# sensor_flexconn.net
KiCad netlist of a schematic drawn in Altium Designer
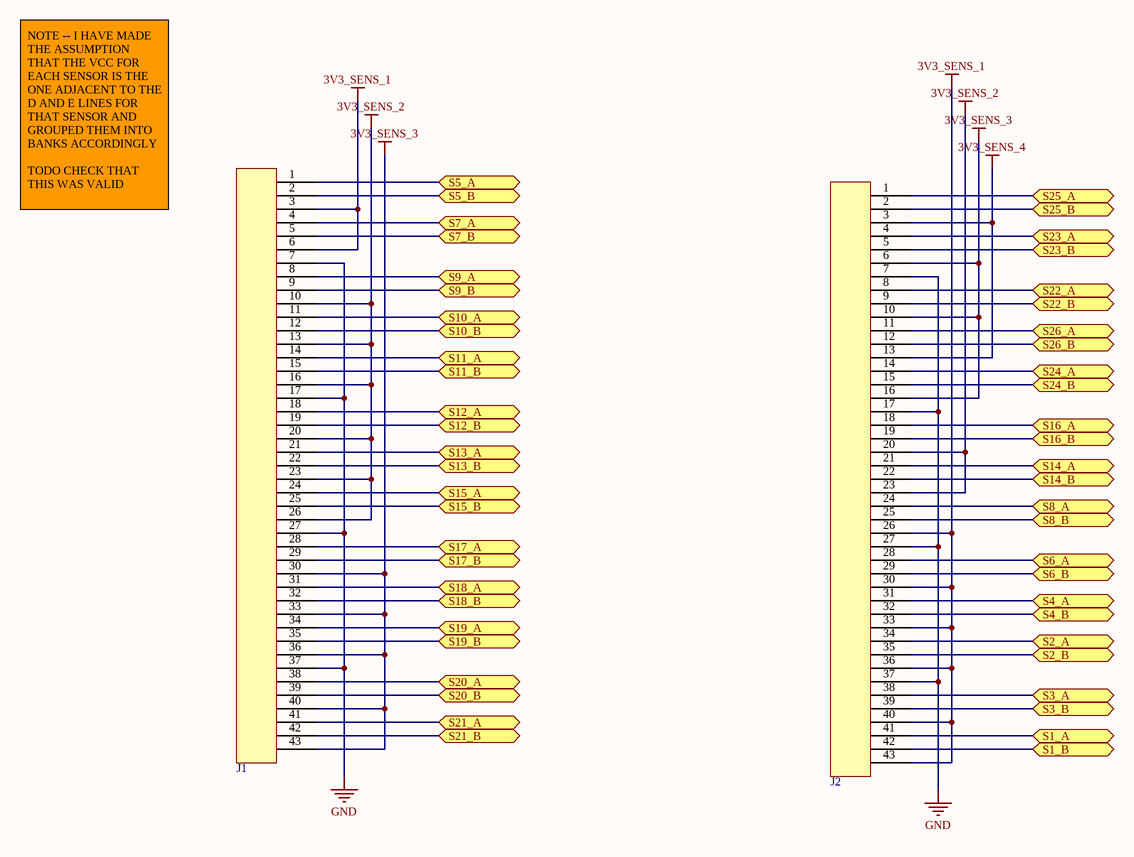
[diagram p0: sensor_flexconn.SchDoc]

(export (version "E")
  (design (tool "Eeschema 10.0.6"))
  (components
    (comp (ref "J1")
      (value "503566-4302")
      (description "FPC Connector, 43P, 0.3mm")
      (libsource (lib "CustomParts") (part "503566-4302"))
    )
    (comp (ref "J2")
      (value "503566-4302")
      (description "FPC Connector, 43P, 0.3mm")
      (libsource (lib "CustomParts") (part "503566-4302"))
    )
  )
  (nets
    (net (code "1") (name "/S1_A") (class "Default")
      (node (ref "J2") (pin "41") (pinfunction "41_41") (pintype "passive"))
    )
    (net (code "2") (name "/S1_B") (class "Default")
      (node (ref "J2") (pin "42") (pinfunction "42_42") (pintype "passive"))
    )
    (net (code "3") (name "/S2_A") (class "Default")
      (node (ref "J2") (pin "34") (pinfunction "34_34") (pintype "passive"))
    )
    (net (code "4") (name "/S2_B") (class "Default")
      (node (ref "J2") (pin "35") (pinfunction "35_35") (pintype "passive"))
    )
    (net (code "5") (name "/S3_A") (class "Default")
      (node (ref "J2") (pin "38") (pinfunction "38_38") (pintype "passive"))
    )
    (net (code "6") (name "/S3_B") (class "Default")
      (node (ref "J2") (pin "39") (pinfunction "39_39") (pintype "passive"))
    )
    (net (code "7") (name "/S4_A") (class "Default")
      (node (ref "J2") (pin "31") (pinfunction "31_31") (pintype "passive"))
    )
    (net (code "8") (name "/S4_B") (class "Default")
      (node (ref "J2") (pin "32") (pinfunction "32_32") (pintype "passive"))
    )
    (net (code "9") (name "/S5_A") (class "Default")
      (node (ref "J1") (pin "1") (pinfunction "1_1") (pintype "passive"))
    )
    (net (code "10") (name "/S5_B") (class "Default")
      (node (ref "J1") (pin "2") (pinfunction "2_2") (pintype "passive"))
    )
    (net (code "11") (name "/S6_A") (class "Default")
      (node (ref "J2") (pin "28") (pinfunction "28_28") (pintype "passive"))
    )
    (net (code "12") (name "/S6_B") (class "Default")
      (node (ref "J2") (pin "29") (pinfunction "29_29") (pintype "passive"))
    )
    (net (code "13") (name "/S7_A") (class "Default")
      (node (ref "J1") (pin "4") (pinfunction "4_4") (pintype "passive"))
    )
    (net (code "14") (name "/S7_B") (class "Default")
      (node (ref "J1") (pin "5") (pinfunction "5_5") (pintype "passive"))
    )
    (net (code "15") (name "/S8_A") (class "Default")
      (node (ref "J2") (pin "24") (pinfunction "24_24") (pintype "passive"))
    )
    (net (code "16") (name "/S8_B") (class "Default")
      (node (ref "J2") (pin "25") (pinfunction "25_25") (pintype "passive"))
    )
    (net (code "17") (name "/S9_A") (class "Default")
      (node (ref "J1") (pin "8") (pinfunction "8_8") (pintype "passive"))
    )
    (net (code "18") (name "/S9_B") (class "Default")
      (node (ref "J1") (pin "9") (pinfunction "9_9") (pintype "passive"))
    )
    (net (code "19") (name "/S10_A") (class "Default")
      (node (ref "J1") (pin "11") (pinfunction "11_11") (pintype "passive"))
    )
    (net (code "20") (name "/S10_B") (class "Default")
      (node (ref "J1") (pin "12") (pinfunction "12_12") (pintype "passive"))
    )
    (net (code "21") (name "/S11_A") (class "Default")
      (node (ref "J1") (pin "14") (pinfunction "14_14") (pintype "passive"))
    )
    (net (code "22") (name "/S11_B") (class "Default")
      (node (ref "J1") (pin "15") (pinfunction "15_15") (pintype "passive"))
    )
    (net (code "23") (name "/S12_A") (class "Default")
      (node (ref "J1") (pin "18") (pinfunction "18_18") (pintype "passive"))
    )
    (net (code "24") (name "/S12_B") (class "Default")
      (node (ref "J1") (pin "19") (pinfunction "19_19") (pintype "passive"))
    )
    (net (code "25") (name "/S13_A") (class "Default")
      (node (ref "J1") (pin "21") (pinfunction "21_21") (pintype "passive"))
    )
    (net (code "26") (name "/S13_B") (class "Default")
      (node (ref "J1") (pin "22") (pinfunction "22_22") (pintype "passive"))
    )
    (net (code "27") (name "/S14_A") (class "Default")
      (node (ref "J2") (pin "21") (pinfunction "21_21") (pintype "passive"))
    )
    (net (code "28") (name "/S14_B") (class "Default")
      (node (ref "J2") (pin "22") (pinfunction "22_22") (pintype "passive"))
    )
    (net (code "29") (name "/S15_A") (class "Default")
      (node (ref "J1") (pin "24") (pinfunction "24_24") (pintype "passive"))
    )
    (net (code "30") (name "/S15_B") (class "Default")
      (node (ref "J1") (pin "25") (pinfunction "25_25") (pintype "passive"))
    )
    (net (code "31") (name "/S16_A") (class "Default")
      (node (ref "J2") (pin "18") (pinfunction "18_18") (pintype "passive"))
    )
    (net (code "32") (name "/S16_B") (class "Default")
      (node (ref "J2") (pin "19") (pinfunction "19_19") (pintype "passive"))
    )
    (net (code "33") (name "/S17_A") (class "Default")
      (node (ref "J1") (pin "28") (pinfunction "28_28") (pintype "passive"))
    )
    (net (code "34") (name "/S17_B") (class "Default")
      (node (ref "J1") (pin "29") (pinfunction "29_29") (pintype "passive"))
    )
    (net (code "35") (name "/S18_A") (class "Default")
      (node (ref "J1") (pin "31") (pinfunction "31_31") (pintype "passive"))
    )
    (net (code "36") (name "/S18_B") (class "Default")
      (node (ref "J1") (pin "32") (pinfunction "32_32") (pintype "passive"))
    )
    (net (code "37") (name "/S19_A") (class "Default")
      (node (ref "J1") (pin "34") (pinfunction "34_34") (pintype "passive"))
    )
    (net (code "38") (name "/S19_B") (class "Default")
      (node (ref "J1") (pin "35") (pinfunction "35_35") (pintype "passive"))
    )
    (net (code "39") (name "/S20_A") (class "Default")
      (node (ref "J1") (pin "38") (pinfunction "38_38") (pintype "passive"))
    )
    (net (code "40") (name "/S20_B") (class "Default")
      (node (ref "J1") (pin "39") (pinfunction "39_39") (pintype "passive"))
    )
    (net (code "41") (name "/S21_A") (class "Default")
      (node (ref "J1") (pin "41") (pinfunction "41_41") (pintype "passive"))
    )
    (net (code "42") (name "/S21_B") (class "Default")
      (node (ref "J1") (pin "42") (pinfunction "42_42") (pintype "passive"))
    )
    (net (code "43") (name "/S22_A") (class "Default")
      (node (ref "J2") (pin "8") (pinfunction "8_8") (pintype "passive"))
    )
    (net (code "44") (name "/S22_B") (class "Default")
      (node (ref "J2") (pin "9") (pinfunction "9_9") (pintype "passive"))
    )
    (net (code "45") (name "/S23_A") (class "Default")
      (node (ref "J2") (pin "4") (pinfunction "4_4") (pintype "passive"))
    )
    (net (code "46") (name "/S23_B") (class "Default")
      (node (ref "J2") (pin "5") (pinfunction "5_5") (pintype "passive"))
    )
    (net (code "47") (name "/S24_A") (class "Default")
      (node (ref "J2") (pin "14") (pinfunction "14_14") (pintype "passive"))
    )
    (net (code "48") (name "/S24_B") (class "Default")
      (node (ref "J2") (pin "15") (pinfunction "15_15") (pintype "passive"))
    )
    (net (code "49") (name "/S25_A") (class "Default")
      (node (ref "J2") (pin "1") (pinfunction "1_1") (pintype "passive"))
    )
    (net (code "50") (name "/S25_B") (class "Default")
      (node (ref "J2") (pin "2") (pinfunction "2_2") (pintype "passive"))
    )
    (net (code "51") (name "/S26_A") (class "Default")
      (node (ref "J2") (pin "11") (pinfunction "11_11") (pintype "passive"))
    )
    (net (code "52") (name "/S26_B") (class "Default")
      (node (ref "J2") (pin "12") (pinfunction "12_12") (pintype "passive"))
    )
    (net (code "53") (name "3V3_SENS_1") (class "Default")
      (node (ref "J1") (pin "3") (pinfunction "3_3") (pintype "passive"))
      (node (ref "J1") (pin "6") (pinfunction "6_6") (pintype "passive"))
      (node (ref "J2") (pin "26") (pinfunction "26_26") (pintype "passive"))
      (node (ref "J2") (pin "30") (pinfunction "30_30") (pintype "passive"))
      (node (ref "J2") (pin "33") (pinfunction "33_33") (pintype "passive"))
      (node (ref "J2") (pin "36") (pinfunction "36_36") (pintype "passive"))
      (node (ref "J2") (pin "40") (pinfunction "40_40") (pintype "passive"))
      (node (ref "J2") (pin "43") (pinfunction "43_43") (pintype "passive"))
    )
    (net (code "54") (name "3V3_SENS_2") (class "Default")
      (node (ref "J1") (pin "10") (pinfunction "10_10") (pintype "passive"))
      (node (ref "J1") (pin "13") (pinfunction "13_13") (pintype "passive"))
      (node (ref "J1") (pin "16") (pinfunction "16_16") (pintype "passive"))
      (node (ref "J1") (pin "20") (pinfunction "20_20") (pintype "passive"))
      (node (ref "J1") (pin "23") (pinfunction "23_23") (pintype "passive"))
      (node (ref "J1") (pin "26") (pinfunction "26_26") (pintype "passive"))
      (node (ref "J2") (pin "20") (pinfunction "20_20") (pintype "passive"))
      (node (ref "J2") (pin "23") (pinfunction "23_23") (pintype "passive"))
    )
    (net (code "55") (name "3V3_SENS_3") (class "Default")
      (node (ref "J1") (pin "30") (pinfunction "30_30") (pintype "passive"))
      (node (ref "J1") (pin "33") (pinfunction "33_33") (pintype "passive"))
      (node (ref "J1") (pin "36") (pinfunction "36_36") (pintype "passive"))
      (node (ref "J1") (pin "40") (pinfunction "40_40") (pintype "passive"))
      (node (ref "J1") (pin "43") (pinfunction "43_43") (pintype "passive"))
      (node (ref "J2") (pin "10") (pinfunction "10_10") (pintype "passive"))
      (node (ref "J2") (pin "16") (pinfunction "16_16") (pintype "passive"))
      (node (ref "J2") (pin "6") (pinfunction "6_6") (pintype "passive"))
    )
    (net (code "56") (name "3V3_SENS_4") (class "Default")
      (node (ref "J2") (pin "13") (pinfunction "13_13") (pintype "passive"))
      (node (ref "J2") (pin "3") (pinfunction "3_3") (pintype "passive"))
    )
    (net (code "57") (name "GND") (class "Default")
      (node (ref "J1") (pin "17") (pinfunction "17_17") (pintype "passive"))
      (node (ref "J1") (pin "27") (pinfunction "27_27") (pintype "passive"))
      (node (ref "J1") (pin "37") (pinfunction "37_37") (pintype "passive"))
      (node (ref "J1") (pin "7") (pinfunction "7_7") (pintype "passive"))
      (node (ref "J2") (pin "17") (pinfunction "17_17") (pintype "passive"))
      (node (ref "J2") (pin "27") (pinfunction "27_27") (pintype "passive"))
      (node (ref "J2") (pin "37") (pinfunction "37_37") (pintype "passive"))
      (node (ref "J2") (pin "7") (pinfunction "7_7") (pintype "passive"))
    )
  )
)
